# BG95_VLT.net
KiCad netlist of a schematic drawn in Altium Designer
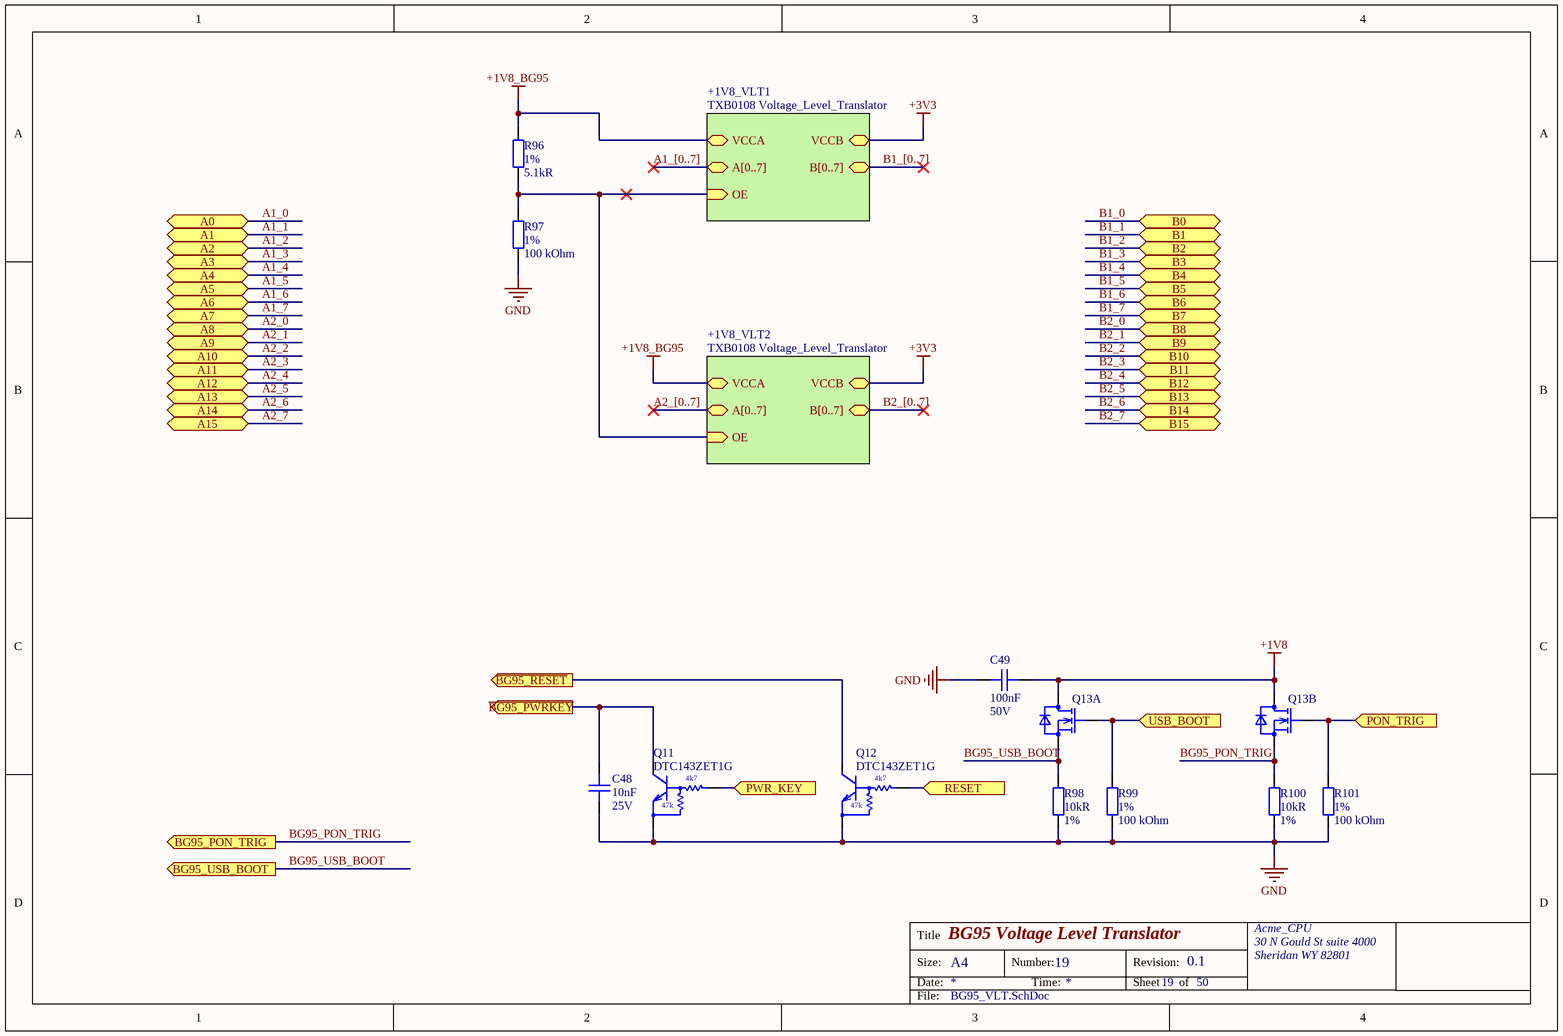
[diagram p0: BG95_VLT.SchDoc]

(export (version "E")
  (design (tool "Eeschema 10.0.6"))
  (components
    (comp (ref "C48")
      (value "CAP CER 10nF 25V X7R 10% 0402")
      (footprint "C0402")
      (description "Cap Cer 10nF 25V X7R 10% 0402")
      (fields
        (field (name "MANUFACTURER") "Kyocera AVX")
        (field (name "MANUFACTURER PART NUMBER") "04023C103KAT2A")
        (field (name "CAPACITANCE") "10nF")
        (field (name "VOLTAGE") "25V")
      )
      (libsource (lib "capacitors_smd") (part "CAP CER 10nF 25V X7R 10% 0402"))
    )
    (comp (ref "C49")
      (value "CAP CER 0.1UF 50V X7R 0402")
      (footprint "C0402")
      (description "0.1µF ±10% 50V Ceramic Capacitor X7R 0402 (1005 Metric)")
      (fields
        (field (name "MANUFACTURER") "TDK")
        (field (name "MANUFACTURER PART NUMBER") "CGA2B3X7R1H104K050BB")
        (field (name "CAPACITANCE") "100nF")
        (field (name "VOLTAGE") "50V")
      )
      (libsource (lib "capacitors_smd") (part "CAP CER 0.1UF 50V X7R 0402"))
    )
    (comp (ref "Q11")
      (value "DTC143ZET1G")
      (footprint "SOT-416FL_ONS")
      (description "Pre-Biased Bipolar Transistor (BJT) NPN - Pre-Biased 50V 100mA  200mW Surface Mount SC-75, SOT-416")
      (fields (field (name "MANUFACTURER") "ON Semiconductor"))
      (libsource (lib "bipolar-junction_transistors_pre_biased") (part "TRANS PREBIAS NPN 200MW SC75"))
    )
    (comp (ref "Q12")
      (value "DTC143ZET1G")
      (footprint "SOT-416FL_ONS")
      (description "Pre-Biased Bipolar Transistor (BJT) NPN - Pre-Biased 50V 100mA  200mW Surface Mount SC-75, SOT-416")
      (fields (field (name "MANUFACTURER") "ON Semiconductor"))
      (libsource (lib "bipolar-junction_transistors_pre_biased") (part "TRANS PREBIAS NPN 200MW SC75"))
    )
    (comp (ref "Q13")
      (value "DMN32D2LV-7")
      (footprint "SON_400UV-7_DIO")
      (description "Mosfet Array 2 N-Channel (Dual) 30V 400mA 400mW Surface Mount SOT-563")
      (fields (field (name "MANUFACTURER") "Diodes"))
      (libsource (lib "mosfets") (part "ARRAY MOSFET 2N-CH 30V 0.4A SOT-563"))
    )
    (comp (ref "R96")
      (value "RES SMD 5.1K OHM 1% 1/16W 0402")
      (footprint "R0402")
      (description "5.1 kOhms ±1% 0.063W, 1/16W Chip Resistor 0402 (1005 Metric) Moisture Resistant Thick Film")
      (fields
        (field (name "MANUFACTURER") "Yageo")
        (field (name "MANUFACTURER PART NUMBER") "RC0402FR-075K1L")
        (field (name "TOLERANCE") "1%")
        (field (name "RESISTANCE") "5.1kR")
      )
      (libsource (lib "resistors_smd") (part "RES SMD 5.1K OHM 1% 1/16W 0402"))
    )
    (comp (ref "R97")
      (value "RES SMD 100K OHM 1% 1/16W 0402")
      (footprint "R0402")
      (description "100 kOhms ±1% 0.063W, 1/16W Chip Resistor 0402 (1005 Metric) Moisture Resistant Thick Film")
      (fields
        (field (name "MANUFACTURER") "Yageo")
        (field (name "MANUFACTURER PART NUMBER") "RC0402FR-07100KL")
        (field (name "TOLERANCE") "1%")
        (field (name "RESISTANCE") "100 kOhm")
      )
      (libsource (lib "resistors_smd") (part "RES SMD 100K OHM 1% 1/16W 0402"))
    )
    (comp (ref "R98")
      (value "RES SMD 10K OHM 1% 1/16W 0402")
      (footprint "R0402")
      (description "10 kOhms ±1% 0.063W, 1/16W Chip Resistor 0402 (1005 Metric) Moisture Resistant Thick Film")
      (fields
        (field (name "MANUFACTURER") "Yageo")
        (field (name "MANUFACTURER PART NUMBER") "RC0402FR-0710KP")
        (field (name "RESISTANCE") "10kR")
        (field (name "TOLERANCE") "1%")
      )
      (libsource (lib "resistors_smd") (part "RES SMD 10K OHM 1% 1/16W 0402"))
    )
    (comp (ref "R99")
      (value "RES SMD 100K OHM 1% 1/16W 0402")
      (footprint "R0402")
      (description "100 kOhms ±1% 0.063W, 1/16W Chip Resistor 0402 (1005 Metric) Moisture Resistant Thick Film")
      (fields
        (field (name "MANUFACTURER") "Yageo")
        (field (name "MANUFACTURER PART NUMBER") "RC0402FR-07100KL")
        (field (name "TOLERANCE") "1%")
        (field (name "RESISTANCE") "100 kOhm")
      )
      (libsource (lib "resistors_smd") (part "RES SMD 100K OHM 1% 1/16W 0402"))
    )
    (comp (ref "R100")
      (value "RES SMD 10K OHM 1% 1/16W 0402")
      (footprint "R0402")
      (description "10 kOhms ±1% 0.063W, 1/16W Chip Resistor 0402 (1005 Metric) Moisture Resistant Thick Film")
      (fields
        (field (name "MANUFACTURER") "Yageo")
        (field (name "MANUFACTURER PART NUMBER") "RC0402FR-0710KP")
        (field (name "RESISTANCE") "10kR")
        (field (name "TOLERANCE") "1%")
      )
      (libsource (lib "resistors_smd") (part "RES SMD 10K OHM 1% 1/16W 0402"))
    )
    (comp (ref "R101")
      (value "RES SMD 100K OHM 1% 1/16W 0402")
      (footprint "R0402")
      (description "100 kOhms ±1% 0.063W, 1/16W Chip Resistor 0402 (1005 Metric) Moisture Resistant Thick Film")
      (fields
        (field (name "MANUFACTURER") "Yageo")
        (field (name "MANUFACTURER PART NUMBER") "RC0402FR-07100KL")
        (field (name "TOLERANCE") "1%")
        (field (name "RESISTANCE") "100 kOhm")
      )
      (libsource (lib "resistors_smd") (part "RES SMD 100K OHM 1% 1/16W 0402"))
    )
  )
  (nets
    (net (code "1") (name "+1V8") (class "Default")
      (node (ref "C49") (pin "2") (pinfunction "2_2") (pintype "passive"))
      (node (ref "Q13") (pin "3") (pinfunction "D_3") (pintype "passive"))
      (node (ref "Q13") (pin "6") (pinfunction "D_6") (pintype "passive"))
    )
    (net (code "2") (name "+1V8_BG95") (class "Default")
      (node (ref "R96") (pin "1") (pinfunction "1_1") (pintype "passive"))
    )
    (net (code "40") (name "/BG95_PON_TRIG") (class "Default")
      (node (ref "Q13") (pin "4") (pinfunction "S_4") (pintype "passive"))
      (node (ref "R100") (pin "1") (pinfunction "1_1") (pintype "passive"))
    )
    (net (code "41") (name "/BG95_PWRKEY") (class "Default")
      (node (ref "C48") (pin "2") (pinfunction "2_2") (pintype "passive"))
      (node (ref "Q11") (pin "3") (pinfunction "C_3") (pintype "passive"))
    )
    (net (code "42") (name "/BG95_RESET") (class "Default")
      (node (ref "Q12") (pin "3") (pinfunction "C_3") (pintype "passive"))
    )
    (net (code "43") (name "/BG95_USB_BOOT") (class "Default")
      (node (ref "Q13") (pin "1") (pinfunction "S_1") (pintype "passive"))
      (node (ref "R98") (pin "1") (pinfunction "1_1") (pintype "passive"))
    )
    (net (code "44") (name "/OE") (class "Default")
      (node (ref "R96") (pin "2") (pinfunction "2_2") (pintype "passive"))
      (node (ref "R97") (pin "2") (pinfunction "2_2") (pintype "passive"))
    )
    (net (code "45") (name "/PON_TRIG") (class "Default")
      (node (ref "Q13") (pin "5") (pinfunction "G_5") (pintype "passive"))
      (node (ref "R101") (pin "2") (pinfunction "2_2") (pintype "passive"))
    )
    (net (code "46") (name "/PWR_KEY") (class "Default")
      (node (ref "Q11") (pin "1") (pinfunction "B_1") (pintype "passive"))
    )
    (net (code "47") (name "/RESET") (class "Default")
      (node (ref "Q12") (pin "1") (pinfunction "B_1") (pintype "passive"))
    )
    (net (code "48") (name "/USB_BOOT") (class "Default")
      (node (ref "Q13") (pin "2") (pinfunction "G_2") (pintype "passive"))
      (node (ref "R99") (pin "2") (pinfunction "2_2") (pintype "passive"))
    )
    (net (code "49") (name "GND") (class "Default")
      (node (ref "C48") (pin "1") (pinfunction "1_1") (pintype "passive"))
      (node (ref "C49") (pin "1") (pinfunction "1_1") (pintype "passive"))
      (node (ref "Q11") (pin "2") (pinfunction "E_2") (pintype "passive"))
      (node (ref "Q12") (pin "2") (pinfunction "E_2") (pintype "passive"))
      (node (ref "R100") (pin "2") (pinfunction "2_2") (pintype "passive"))
      (node (ref "R101") (pin "1") (pinfunction "1_1") (pintype "passive"))
      (node (ref "R97") (pin "1") (pinfunction "1_1") (pintype "passive"))
      (node (ref "R98") (pin "2") (pinfunction "2_2") (pintype "passive"))
      (node (ref "R99") (pin "1") (pinfunction "1_1") (pintype "passive"))
    )
  )
)
